# HypnosV3_5.net
KiCad netlist of a schematic drawn in EAGLE
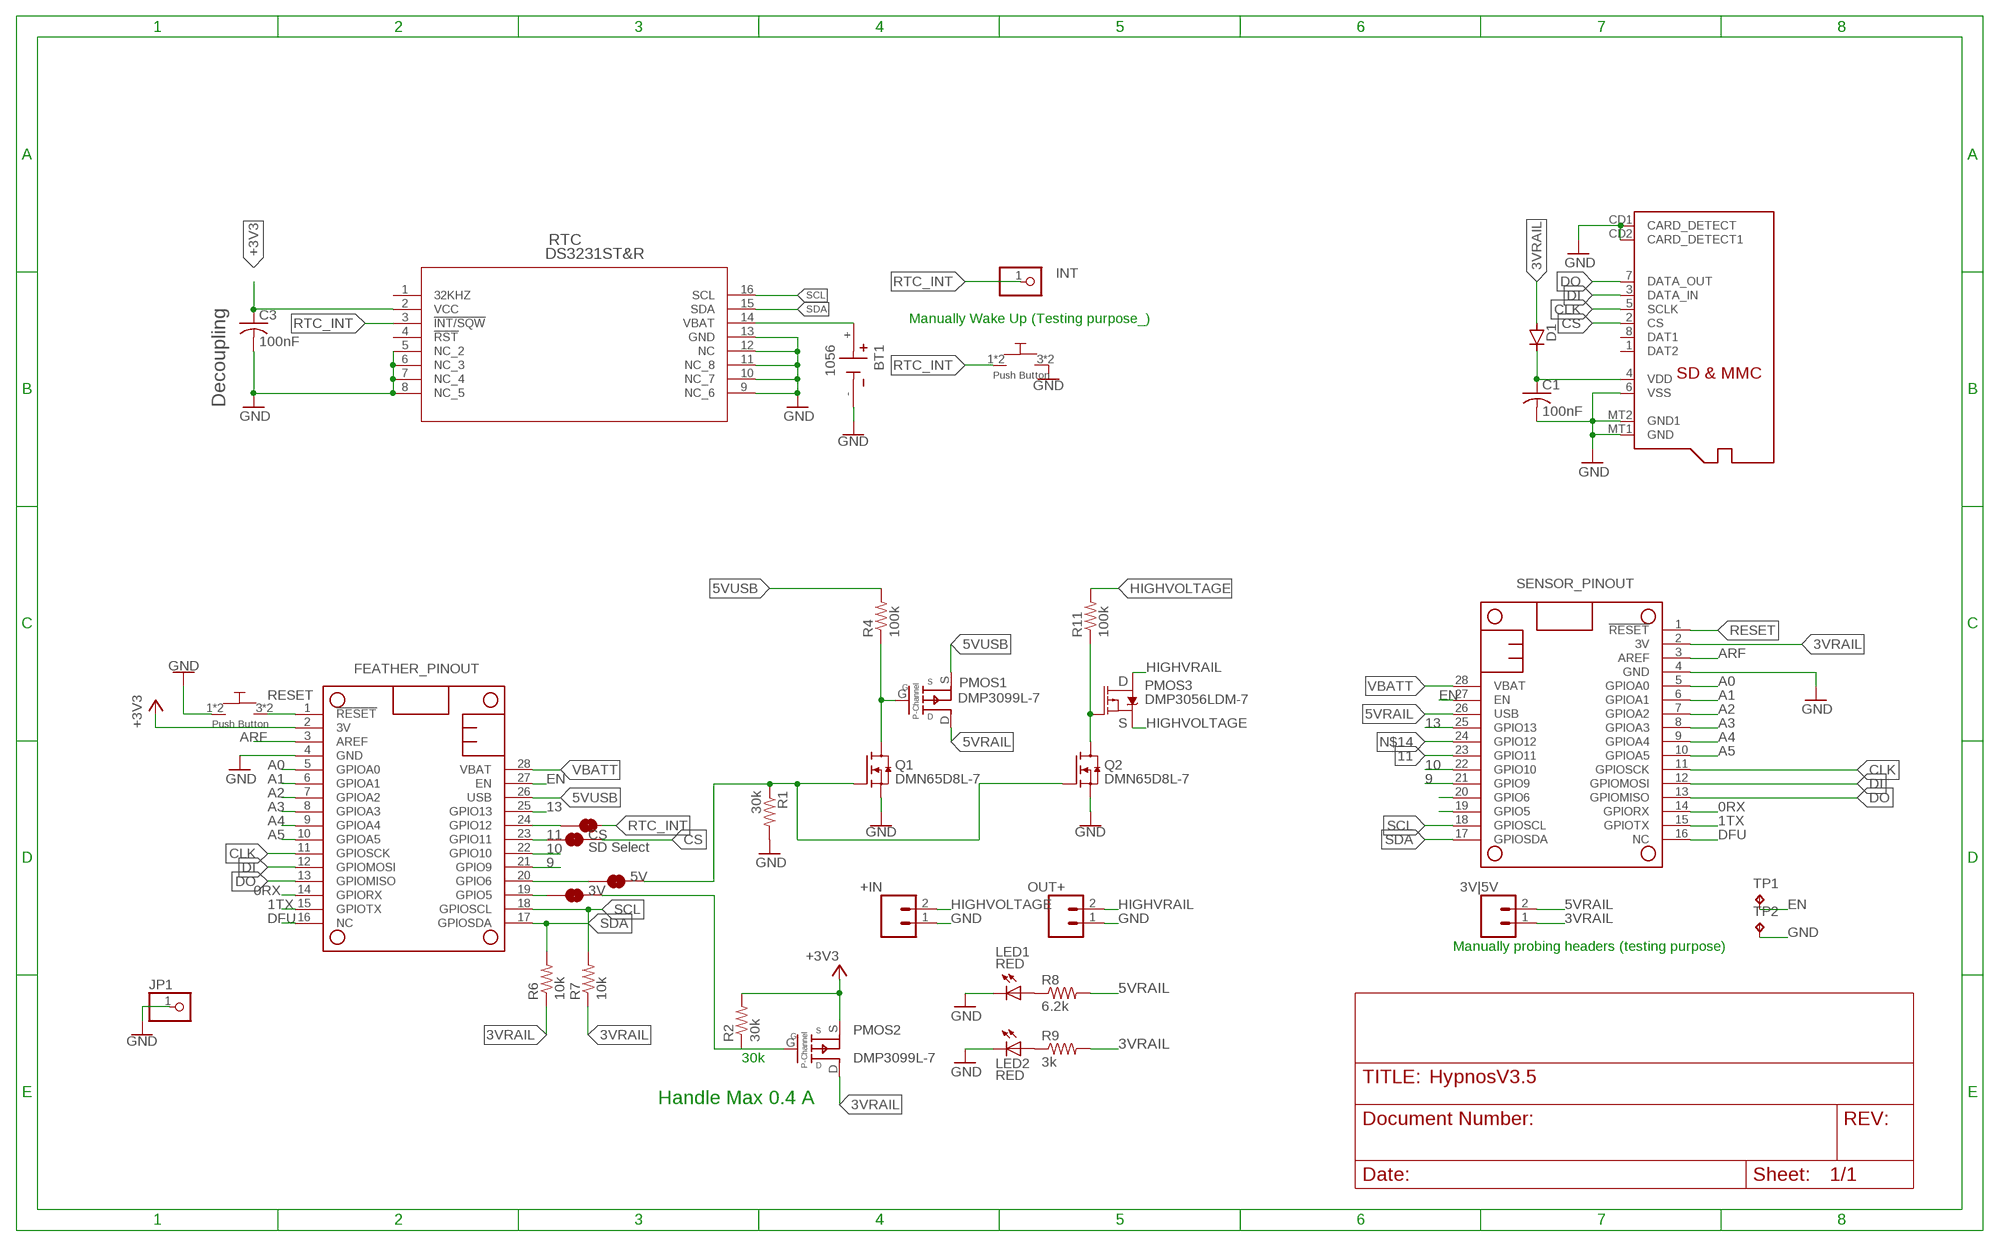
[diagram p0: schematic, sheet 1]

(export (version "E")
  (design (tool "Eeschema 10.0.6"))
  (components
    (comp (ref "+IN")
      (value "HIGHV-IN")
      (footprint "eagle-import:1X02_NO_SILK")
      (libsource (lib "eagle-import") (part "CONN_021X02_NO_SILK"))
    )
    (comp (ref "3V")
      (value "JUMPER-SMT_2_NC_TRACE_SILK")
      (footprint "eagle-import:SMT-JUMPER_2_NC_TRACE_SILK")
      (libsource (lib "eagle-import") (part "JUMPER-SMT_2_NC_TRACE_SILK"))
    )
    (comp (ref "3V|5V")
      (value "CONN_021X02_NO_SILK")
      (footprint "eagle-import:1X02_NO_SILK")
      (libsource (lib "eagle-import") (part "CONN_021X02_NO_SILK"))
    )
    (comp (ref "5V")
      (value "JUMPER-SMT_2_NC_TRACE_SILK")
      (footprint "eagle-import:SMT-JUMPER_2_NC_TRACE_SILK")
      (libsource (lib "eagle-import") (part "JUMPER-SMT_2_NC_TRACE_SILK"))
    )
    (comp (ref "BT1")
      (value "1056")
      (footprint "eagle-import:BAT_1056")
      (fields
        (field (name "DIGI-KEY_PART_NUMBER") "36-1056-ND")
        (field (name "MF") "Keystone Electronics Corp.")
      )
      (libsource (lib "eagle-import") (part "1056"))
    )
    (comp (ref "C1")
      (value "100nF")
      (footprint "eagle-import:C1206")
      (libsource (lib "eagle-import") (part "C-USC1206"))
    )
    (comp (ref "C3")
      (value "100nF")
      (footprint "eagle-import:C1206")
      (libsource (lib "eagle-import") (part "C-USC1206"))
    )
    (comp (ref "CS")
      (value "SD Select")
      (footprint "eagle-import:SMT-JUMPER_2_NC_TRACE_SILK")
      (libsource (lib "eagle-import") (part "JUMPER-SMT_2_NC_TRACE_SILK"))
    )
    (comp (ref "D1")
      (value "D-SOD123")
      (footprint "eagle-import:SOD123")
      (libsource (lib "eagle-import") (part "D-SOD123"))
    )
    (comp (ref "FEATHERWING")
      (value "SENSOR_PINOUT")
      (footprint "eagle-import:FEATHERWING")
      (libsource (lib "eagle-import") (part "powerboard_FEATHERWING"))
    )
    (comp (ref "INT")
      (value "PINHD-1X1CB")
      (footprint "eagle-import:1X01-CLEANBIG")
      (libsource (lib "eagle-import") (part "PINHD-1X1CB"))
    )
    (comp (ref "JP1")
      (value "PINHD-1X1CB")
      (footprint "eagle-import:1X01-CLEANBIG")
      (libsource (lib "eagle-import") (part "PINHD-1X1CB"))
    )
    (comp (ref "LED1")
      (value "RED")
      (footprint "eagle-import:CHIPLED_0805")
      (libsource (lib "eagle-import") (part "LEDCHIPLED_0805"))
    )
    (comp (ref "LED2")
      (value "RED")
      (footprint "eagle-import:CHIPLED_0805")
      (libsource (lib "eagle-import") (part "LEDCHIPLED_0805"))
    )
    (comp (ref "MICROSD")
      (value "MICROSD")
      (footprint "eagle-import:MICROSD")
      (libsource (lib "eagle-import") (part "MICROSD"))
    )
    (comp (ref "MS2")
      (value "FEATHER_PINOUT")
      (footprint "eagle-import:FEATHERWING")
      (libsource (lib "eagle-import") (part "FEATHERWING"))
    )
    (comp (ref "OUT+")
      (value "HIGHV-OUT")
      (footprint "eagle-import:1X02_NO_SILK")
      (libsource (lib "eagle-import") (part "CONN_021X02_NO_SILK"))
    )
    (comp (ref "PMOS1")
      (value "DMP3099L-7")
      (footprint "eagle-import:SOT-23-3")
      (libsource (lib "eagle-import") (part "SSM3J3228R"))
    )
    (comp (ref "PMOS2")
      (value "DMP3099L-7")
      (footprint "eagle-import:SOT-23-3")
      (libsource (lib "eagle-import") (part "SSM3J3228R"))
    )
    (comp (ref "PMOS3")
      (value "DMP3056LDM-7")
      (footprint "eagle-import:SOT23-6")
      (libsource (lib "eagle-import") (part "P-MOSFET"))
    )
    (comp (ref "Q1")
      (value "DMN65D8L-7")
      (footprint "eagle-import:SOT23-S")
      (libsource (lib "eagle-import") (part "NMOS"))
    )
    (comp (ref "Q2")
      (value "DMN65D8L-7")
      (footprint "eagle-import:SOT23-S")
      (libsource (lib "eagle-import") (part "NMOS"))
    )
    (comp (ref "R1")
      (value "30k")
      (footprint "eagle-import:RES_1206")
      (fields
        (field (name "DIGIKEY_PART_NUMBER") "WSLP-.05TR-ND")
        (field (name "MANUFACTURER") "Vishay Dale")
        (field (name "MPN") "WSLP1206R0500FEA")
        (field (name "CREATED_BY") "PCBLayout.com")
      )
      (libsource (lib "eagle-import") (part "WSLP1206R0500FEA"))
    )
    (comp (ref "R2")
      (value "30k")
      (footprint "eagle-import:RES_1206")
      (fields
        (field (name "DIGIKEY_PART_NUMBER") "WSLP-.05TR-ND")
        (field (name "MANUFACTURER") "Vishay Dale")
        (field (name "MPN") "WSLP1206R0500FEA")
        (field (name "CREATED_BY") "PCBLayout.com")
      )
      (libsource (lib "eagle-import") (part "WSLP1206R0500FEA"))
    )
    (comp (ref "R4")
      (value "100k")
      (footprint "eagle-import:RES_1206")
      (fields
        (field (name "DIGIKEY_PART_NUMBER") "WSLP-.05TR-ND")
        (field (name "MANUFACTURER") "Vishay Dale")
        (field (name "MPN") "WSLP1206R0500FEA")
        (field (name "CREATED_BY") "PCBLayout.com")
      )
      (libsource (lib "eagle-import") (part "WSLP1206R0500FEA"))
    )
    (comp (ref "R6")
      (value "10k")
      (footprint "eagle-import:RES_1206")
      (fields
        (field (name "DIGIKEY_PART_NUMBER") "WSLP-.05TR-ND")
        (field (name "MANUFACTURER") "Vishay Dale")
        (field (name "MPN") "WSLP1206R0500FEA")
        (field (name "CREATED_BY") "PCBLayout.com")
      )
      (libsource (lib "eagle-import") (part "WSLP1206R0500FEA"))
    )
    (comp (ref "R7")
      (value "10k")
      (footprint "eagle-import:RES_1206")
      (fields
        (field (name "DIGIKEY_PART_NUMBER") "WSLP-.05TR-ND")
        (field (name "MANUFACTURER") "Vishay Dale")
        (field (name "MPN") "WSLP1206R0500FEA")
        (field (name "CREATED_BY") "PCBLayout.com")
      )
      (libsource (lib "eagle-import") (part "WSLP1206R0500FEA"))
    )
    (comp (ref "R8")
      (value "6.2k")
      (footprint "eagle-import:RES_1206")
      (fields
        (field (name "DIGIKEY_PART_NUMBER") "WSLP-.05TR-ND")
        (field (name "MANUFACTURER") "Vishay Dale")
        (field (name "MPN") "WSLP1206R0500FEA")
        (field (name "CREATED_BY") "PCBLayout.com")
      )
      (libsource (lib "eagle-import") (part "WSLP1206R0500FEA"))
    )
    (comp (ref "R9")
      (value "3k")
      (footprint "eagle-import:RES_1206")
      (fields
        (field (name "DIGIKEY_PART_NUMBER") "WSLP-.05TR-ND")
        (field (name "MANUFACTURER") "Vishay Dale")
        (field (name "MPN") "WSLP1206R0500FEA")
        (field (name "CREATED_BY") "PCBLayout.com")
      )
      (libsource (lib "eagle-import") (part "WSLP1206R0500FEA"))
    )
    (comp (ref "R11")
      (value "100k")
      (footprint "eagle-import:RES_1206")
      (fields
        (field (name "DIGIKEY_PART_NUMBER") "WSLP-.05TR-ND")
        (field (name "MANUFACTURER") "Vishay Dale")
        (field (name "MPN") "WSLP1206R0500FEA")
        (field (name "CREATED_BY") "PCBLayout.com")
      )
      (libsource (lib "eagle-import") (part "WSLP1206R0500FEA"))
    )
    (comp (ref "RTC")
      (value "DS3231ST&R")
      (footprint "eagle-import:21-0042B_16")
      (fields (field (name "MANUFACTURER_PART_NUMBER") "DS3231S#T&R"))
      (libsource (lib "eagle-import") (part "DS3231ST&R"))
    )
    (comp (ref "RTC_INT")
      (value "JUMPER-SMT_2_NC_TRACE_SILK")
      (footprint "eagle-import:SMT-JUMPER_2_NC_TRACE_SILK")
      (libsource (lib "eagle-import") (part "JUMPER-SMT_2_NC_TRACE_SILK"))
    )
    (comp (ref "TP1")
      (value "TPTP16R")
      (footprint "eagle-import:TP16R")
      (libsource (lib "eagle-import") (part "TPTP16R"))
    )
    (comp (ref "TP2")
      (value "TPTP16R")
      (footprint "eagle-import:TP16R")
      (libsource (lib "eagle-import") (part "TPTP16R"))
    )
    (comp (ref "U$1")
      (value "PUSH_BUTTON")
      (footprint "eagle-import:PUSHBUTTON_SMD")
      (libsource (lib "eagle-import") (part "PUSH_BUTTON"))
    )
    (comp (ref "U$2")
      (value "PUSH_BUTTON")
      (footprint "eagle-import:PUSHBUTTON_SMD")
      (libsource (lib "eagle-import") (part "PUSH_BUTTON"))
    )
  )
  (nets
    (net (code "1") (name "+3V3") (class "Default")
      (node (ref "C3") (pin "1") (pinfunction "1_1") (pintype "passive"))
      (node (ref "MS2") (pin "2") (pinfunction "3V_2") (pintype "power_in"))
      (node (ref "PMOS2") (pin "S") (pinfunction "S_S") (pintype "bidirectional"))
      (node (ref "R2") (pin "2") (pinfunction "2_2") (pintype "passive"))
      (node (ref "RTC") (pin "2") (pinfunction "VCC_2") (pintype "power_in"))
    )
    (net (code "2") (name "/0RX") (class "Default")
      (node (ref "FEATHERWING") (pin "14") (pinfunction "GPIORX_14") (pintype "bidirectional"))
      (node (ref "MS2") (pin "14") (pinfunction "GPIORX_14") (pintype "bidirectional"))
    )
    (net (code "3") (name "/1TX") (class "Default")
      (node (ref "FEATHERWING") (pin "15") (pinfunction "GPIOTX_15") (pintype "bidirectional"))
      (node (ref "MS2") (pin "15") (pinfunction "GPIOTX_15") (pintype "bidirectional"))
    )
    (net (code "4") (name "/9") (class "Default")
      (node (ref "FEATHERWING") (pin "21") (pinfunction "GPIO9_21") (pintype "bidirectional"))
      (node (ref "MS2") (pin "21") (pinfunction "GPIO9_21") (pintype "bidirectional"))
    )
    (net (code "5") (name "/10") (class "Default")
      (node (ref "FEATHERWING") (pin "22") (pinfunction "GPIO10_22") (pintype "bidirectional"))
      (node (ref "MS2") (pin "22") (pinfunction "GPIO10_22") (pintype "bidirectional"))
    )
    (net (code "6") (name "/13") (class "Default")
      (node (ref "FEATHERWING") (pin "25") (pinfunction "GPIO13_25") (pintype "bidirectional"))
      (node (ref "MS2") (pin "25") (pinfunction "GPIO13_25") (pintype "bidirectional"))
    )
    (net (code "7") (name "/A0") (class "Default")
      (node (ref "FEATHERWING") (pin "5") (pinfunction "GPIOA0_5") (pintype "bidirectional"))
      (node (ref "MS2") (pin "5") (pinfunction "GPIOA0_5") (pintype "bidirectional"))
    )
    (net (code "8") (name "/A1") (class "Default")
      (node (ref "FEATHERWING") (pin "6") (pinfunction "GPIOA1_6") (pintype "bidirectional"))
      (node (ref "MS2") (pin "6") (pinfunction "GPIOA1_6") (pintype "bidirectional"))
    )
    (net (code "9") (name "/A2") (class "Default")
      (node (ref "FEATHERWING") (pin "7") (pinfunction "GPIOA2_7") (pintype "bidirectional"))
      (node (ref "MS2") (pin "7") (pinfunction "GPIOA2_7") (pintype "bidirectional"))
    )
    (net (code "10") (name "/A3") (class "Default")
      (node (ref "FEATHERWING") (pin "8") (pinfunction "GPIOA3_8") (pintype "bidirectional"))
      (node (ref "MS2") (pin "8") (pinfunction "GPIOA3_8") (pintype "bidirectional"))
    )
    (net (code "11") (name "/A4") (class "Default")
      (node (ref "FEATHERWING") (pin "9") (pinfunction "GPIOA4_9") (pintype "bidirectional"))
      (node (ref "MS2") (pin "9") (pinfunction "GPIOA4_9") (pintype "bidirectional"))
    )
    (net (code "12") (name "/A5") (class "Default")
      (node (ref "FEATHERWING") (pin "10") (pinfunction "GPIOA5_10") (pintype "bidirectional"))
      (node (ref "MS2") (pin "10") (pinfunction "GPIOA5_10") (pintype "bidirectional"))
    )
    (net (code "13") (name "/ARF") (class "Default")
      (node (ref "FEATHERWING") (pin "3") (pinfunction "AREF_3") (pintype "passive"))
      (node (ref "MS2") (pin "3") (pinfunction "AREF_3") (pintype "passive"))
    )
    (net (code "14") (name "/DFU") (class "Default")
      (node (ref "FEATHERWING") (pin "16") (pinfunction "NC_16") (pintype "passive"))
      (node (ref "MS2") (pin "16") (pinfunction "NC_16") (pintype "passive"))
    )
    (net (code "15") (name "/EN") (class "Default")
      (node (ref "FEATHERWING") (pin "27") (pinfunction "EN_27") (pintype "passive"))
      (node (ref "MS2") (pin "27") (pinfunction "EN_27") (pintype "passive"))
      (node (ref "TP1") (pin "TP") (pinfunction "TP_TP") (pintype "input"))
    )
    (net (code "16") (name "/HIGHVRAIL") (class "Default")
      (node (ref "OUT+") (pin "2") (pinfunction "2_2") (pintype "passive"))
      (node (ref "PMOS3") (pin "1") (pinfunction "D_1") (pintype "bidirectional"))
      (node (ref "PMOS3") (pin "2") (pinfunction "D_2") (pintype "bidirectional"))
      (node (ref "PMOS3") (pin "5") (pinfunction "D_5") (pintype "bidirectional"))
      (node (ref "PMOS3") (pin "6") (pinfunction "D_6") (pintype "bidirectional"))
    )
    (net (code "17") (name "3VRAIL") (class "Default")
      (node (ref "3V|5V") (pin "1") (pinfunction "1_1") (pintype "passive"))
      (node (ref "D1") (pin "2") (pinfunction "A_2") (pintype "passive"))
      (node (ref "FEATHERWING") (pin "2") (pinfunction "3V_2") (pintype "power_in"))
      (node (ref "PMOS2") (pin "D") (pinfunction "D_D") (pintype "bidirectional"))
      (node (ref "R6") (pin "1") (pinfunction "1_1") (pintype "passive"))
      (node (ref "R7") (pin "1") (pinfunction "1_1") (pintype "passive"))
      (node (ref "R9") (pin "2") (pinfunction "2_2") (pintype "passive"))
    )
    (net (code "18") (name "5VRAIL") (class "Default")
      (node (ref "3V|5V") (pin "2") (pinfunction "2_2") (pintype "passive"))
      (node (ref "FEATHERWING") (pin "26") (pinfunction "USB_26") (pintype "power_in"))
      (node (ref "PMOS1") (pin "D") (pinfunction "D_D") (pintype "bidirectional"))
      (node (ref "R8") (pin "2") (pinfunction "2_2") (pintype "passive"))
    )
    (net (code "19") (name "5VUSB") (class "Default")
      (node (ref "MS2") (pin "26") (pinfunction "USB_26") (pintype "power_in"))
      (node (ref "PMOS1") (pin "S") (pinfunction "S_S") (pintype "bidirectional"))
      (node (ref "R4") (pin "2") (pinfunction "2_2") (pintype "passive"))
    )
    (net (code "20") (name "11") (class "Default")
      (node (ref "CS") (pin "1") (pinfunction "1_1") (pintype "passive"))
      (node (ref "FEATHERWING") (pin "23") (pinfunction "GPIO11_23") (pintype "bidirectional"))
      (node (ref "MS2") (pin "23") (pinfunction "GPIO11_23") (pintype "bidirectional"))
    )
    (net (code "21") (name "CLK") (class "Default")
      (node (ref "FEATHERWING") (pin "11") (pinfunction "GPIOSCK_11") (pintype "bidirectional"))
      (node (ref "MICROSD") (pin "5") (pinfunction "SCLK_5") (pintype "input"))
      (node (ref "MS2") (pin "11") (pinfunction "GPIOSCK_11") (pintype "bidirectional"))
    )
    (net (code "22") (name "CS") (class "Default")
      (node (ref "CS") (pin "2") (pinfunction "2_2") (pintype "passive"))
      (node (ref "MICROSD") (pin "2") (pinfunction "CS_2") (pintype "input"))
    )
    (net (code "23") (name "DI") (class "Default")
      (node (ref "FEATHERWING") (pin "12") (pinfunction "GPIOMOSI_12") (pintype "bidirectional"))
      (node (ref "MICROSD") (pin "3") (pinfunction "DATA_IN_3") (pintype "input"))
      (node (ref "MS2") (pin "12") (pinfunction "GPIOMOSI_12") (pintype "bidirectional"))
    )
    (net (code "24") (name "DO") (class "Default")
      (node (ref "FEATHERWING") (pin "13") (pinfunction "GPIOMISO_13") (pintype "bidirectional"))
      (node (ref "MICROSD") (pin "7") (pinfunction "DATA_OUT_7") (pintype "output"))
      (node (ref "MS2") (pin "13") (pinfunction "GPIOMISO_13") (pintype "bidirectional"))
    )
    (net (code "25") (name "GND") (class "Default")
      (node (ref "+IN") (pin "1") (pinfunction "1_1") (pintype "passive"))
      (node (ref "BT1") (pin "-") (pinfunction "-_-") (pintype "passive"))
      (node (ref "C1") (pin "2") (pinfunction "2_2") (pintype "passive"))
      (node (ref "C3") (pin "2") (pinfunction "2_2") (pintype "passive"))
      (node (ref "FEATHERWING") (pin "4") (pinfunction "GND_4") (pintype "power_in"))
      (node (ref "JP1") (pin "1") (pinfunction "1_1") (pintype "passive"))
      (node (ref "LED1") (pin "C") (pinfunction "C_C") (pintype "passive"))
      (node (ref "LED2") (pin "C") (pinfunction "C_C") (pintype "passive"))
      (node (ref "MICROSD") (pin "6") (pinfunction "VSS_6") (pintype "power_in"))
      (node (ref "MICROSD") (pin "CD1") (pinfunction "CARD_DETECT_CD1") (pintype "passive"))
      (node (ref "MICROSD") (pin "CD2") (pinfunction "CARD_DETECT1_CD2") (pintype "passive"))
      (node (ref "MICROSD") (pin "MT1") (pinfunction "GND_MT1") (pintype "power_in"))
      (node (ref "MICROSD") (pin "MT2") (pinfunction "GND1_MT2") (pintype "power_in"))
      (node (ref "MS2") (pin "4") (pinfunction "GND_4") (pintype "power_in"))
      (node (ref "OUT+") (pin "1") (pinfunction "1_1") (pintype "passive"))
      (node (ref "Q1") (pin "2") (pinfunction "S_2") (pintype "passive"))
      (node (ref "Q2") (pin "2") (pinfunction "S_2") (pintype "passive"))
      (node (ref "R1") (pin "2") (pinfunction "2_2") (pintype "passive"))
      (node (ref "RTC") (pin "10") (pinfunction "NC_7_10") (pintype "passive"))
      (node (ref "RTC") (pin "11") (pinfunction "NC_8_11") (pintype "passive"))
      (node (ref "RTC") (pin "12") (pinfunction "NC_12") (pintype "passive"))
      (node (ref "RTC") (pin "13") (pinfunction "GND_13") (pintype "power_in"))
      (node (ref "RTC") (pin "5") (pinfunction "NC_2_5") (pintype "passive"))
      (node (ref "RTC") (pin "6") (pinfunction "NC_3_6") (pintype "passive"))
      (node (ref "RTC") (pin "7") (pinfunction "NC_4_7") (pintype "passive"))
      (node (ref "RTC") (pin "8") (pinfunction "NC_5_8") (pintype "passive"))
      (node (ref "RTC") (pin "9") (pinfunction "NC_6_9") (pintype "passive"))
      (node (ref "TP2") (pin "TP") (pinfunction "TP_TP") (pintype "input"))
      (node (ref "U$1") (pin "1") (pinfunction "P$1_1") (pintype "bidirectional"))
      (node (ref "U$1") (pin "2") (pinfunction "P$1_2") (pintype "bidirectional"))
      (node (ref "U$2") (pin "3") (pinfunction "P$2_3") (pintype "bidirectional"))
      (node (ref "U$2") (pin "4") (pinfunction "P$2_4") (pintype "bidirectional"))
    )
    (net (code "26") (name "HIGHVOLTAGE") (class "Default")
      (node (ref "+IN") (pin "2") (pinfunction "2_2") (pintype "passive"))
      (node (ref "PMOS3") (pin "4") (pinfunction "S_4") (pintype "bidirectional"))
      (node (ref "R11") (pin "2") (pinfunction "2_2") (pintype "passive"))
    )
    (net (code "27") (name "N$14") (class "Default")
      (node (ref "FEATHERWING") (pin "24") (pinfunction "GPIO12_24") (pintype "bidirectional"))
      (node (ref "MS2") (pin "24") (pinfunction "GPIO12_24") (pintype "bidirectional"))
      (node (ref "RTC_INT") (pin "1") (pinfunction "1_1") (pintype "passive"))
    )
    (net (code "28") (name "Net-(3V-Pad2)") (class "Default")
      (node (ref "3V") (pin "2") (pinfunction "2_2") (pintype "passive"))
      (node (ref "PMOS2") (pin "G") (pinfunction "G_G") (pintype "bidirectional"))
      (node (ref "R2") (pin "1") (pinfunction "1_1") (pintype "passive"))
    )
    (net (code "29") (name "Net-(D1-C)") (class "Default")
      (node (ref "C1") (pin "1") (pinfunction "1_1") (pintype "passive"))
      (node (ref "D1") (pin "1") (pinfunction "C_1") (pintype "passive"))
      (node (ref "MICROSD") (pin "4") (pinfunction "VDD_4") (pintype "power_in"))
    )
    (net (code "30") (name "Net-(LED1-PadA)") (class "Default")
      (node (ref "LED1") (pin "A") (pinfunction "A_A") (pintype "passive"))
      (node (ref "R8") (pin "1") (pinfunction "1_1") (pintype "passive"))
    )
    (net (code "31") (name "Net-(LED2-PadA)") (class "Default")
      (node (ref "LED2") (pin "A") (pinfunction "A_A") (pintype "passive"))
      (node (ref "R9") (pin "1") (pinfunction "1_1") (pintype "passive"))
    )
    (net (code "32") (name "Net-(MS2-GPIO5)") (class "Default")
      (node (ref "3V") (pin "1") (pinfunction "1_1") (pintype "passive"))
      (node (ref "MS2") (pin "19") (pinfunction "GPIO5_19") (pintype "bidirectional"))
    )
    (net (code "33") (name "Net-(MS2-GPIO6)") (class "Default")
      (node (ref "5V") (pin "1") (pinfunction "1_1") (pintype "passive"))
      (node (ref "MS2") (pin "20") (pinfunction "GPIO6_20") (pintype "bidirectional"))
    )
    (net (code "34") (name "Net-(PMOS3-G)") (class "Default")
      (node (ref "PMOS3") (pin "3") (pinfunction "G_3") (pintype "bidirectional"))
      (node (ref "Q2") (pin "3") (pinfunction "D_3") (pintype "passive"))
      (node (ref "R11") (pin "1") (pinfunction "1_1") (pintype "passive"))
    )
    (net (code "35") (name "Net-(Q1-D)") (class "Default")
      (node (ref "PMOS1") (pin "G") (pinfunction "G_G") (pintype "bidirectional"))
      (node (ref "Q1") (pin "3") (pinfunction "D_3") (pintype "passive"))
      (node (ref "R4") (pin "1") (pinfunction "1_1") (pintype "passive"))
    )
    (net (code "36") (name "Net-(Q1-G)") (class "Default")
      (node (ref "5V") (pin "2") (pinfunction "2_2") (pintype "passive"))
      (node (ref "Q1") (pin "1") (pinfunction "G_1") (pintype "passive"))
      (node (ref "Q2") (pin "1") (pinfunction "G_1") (pintype "passive"))
      (node (ref "R1") (pin "1") (pinfunction "1_1") (pintype "passive"))
    )
    (net (code "37") (name "Net-(RTC-VBAT)") (class "Default")
      (node (ref "BT1") (pin "+") (pinfunction "+_+") (pintype "passive"))
      (node (ref "RTC") (pin "14") (pinfunction "VBAT_14") (pintype "power_in"))
    )
    (net (code "38") (name "RESET") (class "Default")
      (node (ref "FEATHERWING") (pin "1") (pinfunction "~{RESET}_1") (pintype "input"))
      (node (ref "MS2") (pin "1") (pinfunction "~{RESET}_1") (pintype "input"))
      (node (ref "U$1") (pin "3") (pinfunction "P$2_3") (pintype "bidirectional"))
      (node (ref "U$1") (pin "4") (pinfunction "P$2_4") (pintype "bidirectional"))
    )
    (net (code "39") (name "RTC_INT") (class "Default")
      (node (ref "INT") (pin "1") (pinfunction "1_1") (pintype "passive"))
      (node (ref "RTC") (pin "3") (pinfunction "~{INT/SQW}_3") (pintype "passive"))
      (node (ref "RTC_INT") (pin "2") (pinfunction "2_2") (pintype "passive"))
      (node (ref "U$2") (pin "1") (pinfunction "P$1_1") (pintype "bidirectional"))
      (node (ref "U$2") (pin "2") (pinfunction "P$1_2") (pintype "bidirectional"))
    )
    (net (code "40") (name "SCL") (class "Default")
      (node (ref "FEATHERWING") (pin "18") (pinfunction "GPIOSCL_18") (pintype "bidirectional"))
      (node (ref "MS2") (pin "18") (pinfunction "GPIOSCL_18") (pintype "bidirectional"))
      (node (ref "R7") (pin "2") (pinfunction "2_2") (pintype "passive"))
      (node (ref "RTC") (pin "16") (pinfunction "SCL_16") (pintype "passive"))
    )
    (net (code "41") (name "SDA") (class "Default")
      (node (ref "FEATHERWING") (pin "17") (pinfunction "GPIOSDA_17") (pintype "bidirectional"))
      (node (ref "MS2") (pin "17") (pinfunction "GPIOSDA_17") (pintype "bidirectional"))
      (node (ref "R6") (pin "2") (pinfunction "2_2") (pintype "passive"))
      (node (ref "RTC") (pin "15") (pinfunction "SDA_15") (pintype "passive"))
    )
    (net (code "42") (name "VBATT") (class "Default")
      (node (ref "FEATHERWING") (pin "28") (pinfunction "VBAT_28") (pintype "power_in"))
      (node (ref "MS2") (pin "28") (pinfunction "VBAT_28") (pintype "power_in"))
    )
    (net (code "43") (name "unconnected-(FEATHERWING-GPIO5-Pad19)") (class "Default")
      (node (ref "FEATHERWING") (pin "19") (pinfunction "GPIO5_19") (pintype "bidirectional"))
    )
    (net (code "44") (name "unconnected-(FEATHERWING-GPIO6-Pad20)") (class "Default")
      (node (ref "FEATHERWING") (pin "20") (pinfunction "GPIO6_20") (pintype "bidirectional"))
    )
    (net (code "45") (name "unconnected-(MICROSD-DAT1-Pad8)") (class "Default")
      (node (ref "MICROSD") (pin "8") (pinfunction "DAT1_8") (pintype "bidirectional"))
    )
    (net (code "46") (name "unconnected-(MICROSD-DAT2-Pad1)") (class "Default")
      (node (ref "MICROSD") (pin "1") (pinfunction "DAT2_1") (pintype "bidirectional"))
    )
    (net (code "47") (name "unconnected-(RTC-32KHZ-Pad1)") (class "Default")
      (node (ref "RTC") (pin "1") (pinfunction "32KHZ_1") (pintype "passive"))
    )
    (net (code "48") (name "unconnected-(RTC-~{RST}-Pad4)") (class "Default")
      (node (ref "RTC") (pin "4") (pinfunction "~{RST}_4") (pintype "passive"))
    )
  )
)
